# I2C_MUX.net
KiCad netlist of a schematic drawn in Altium Designer
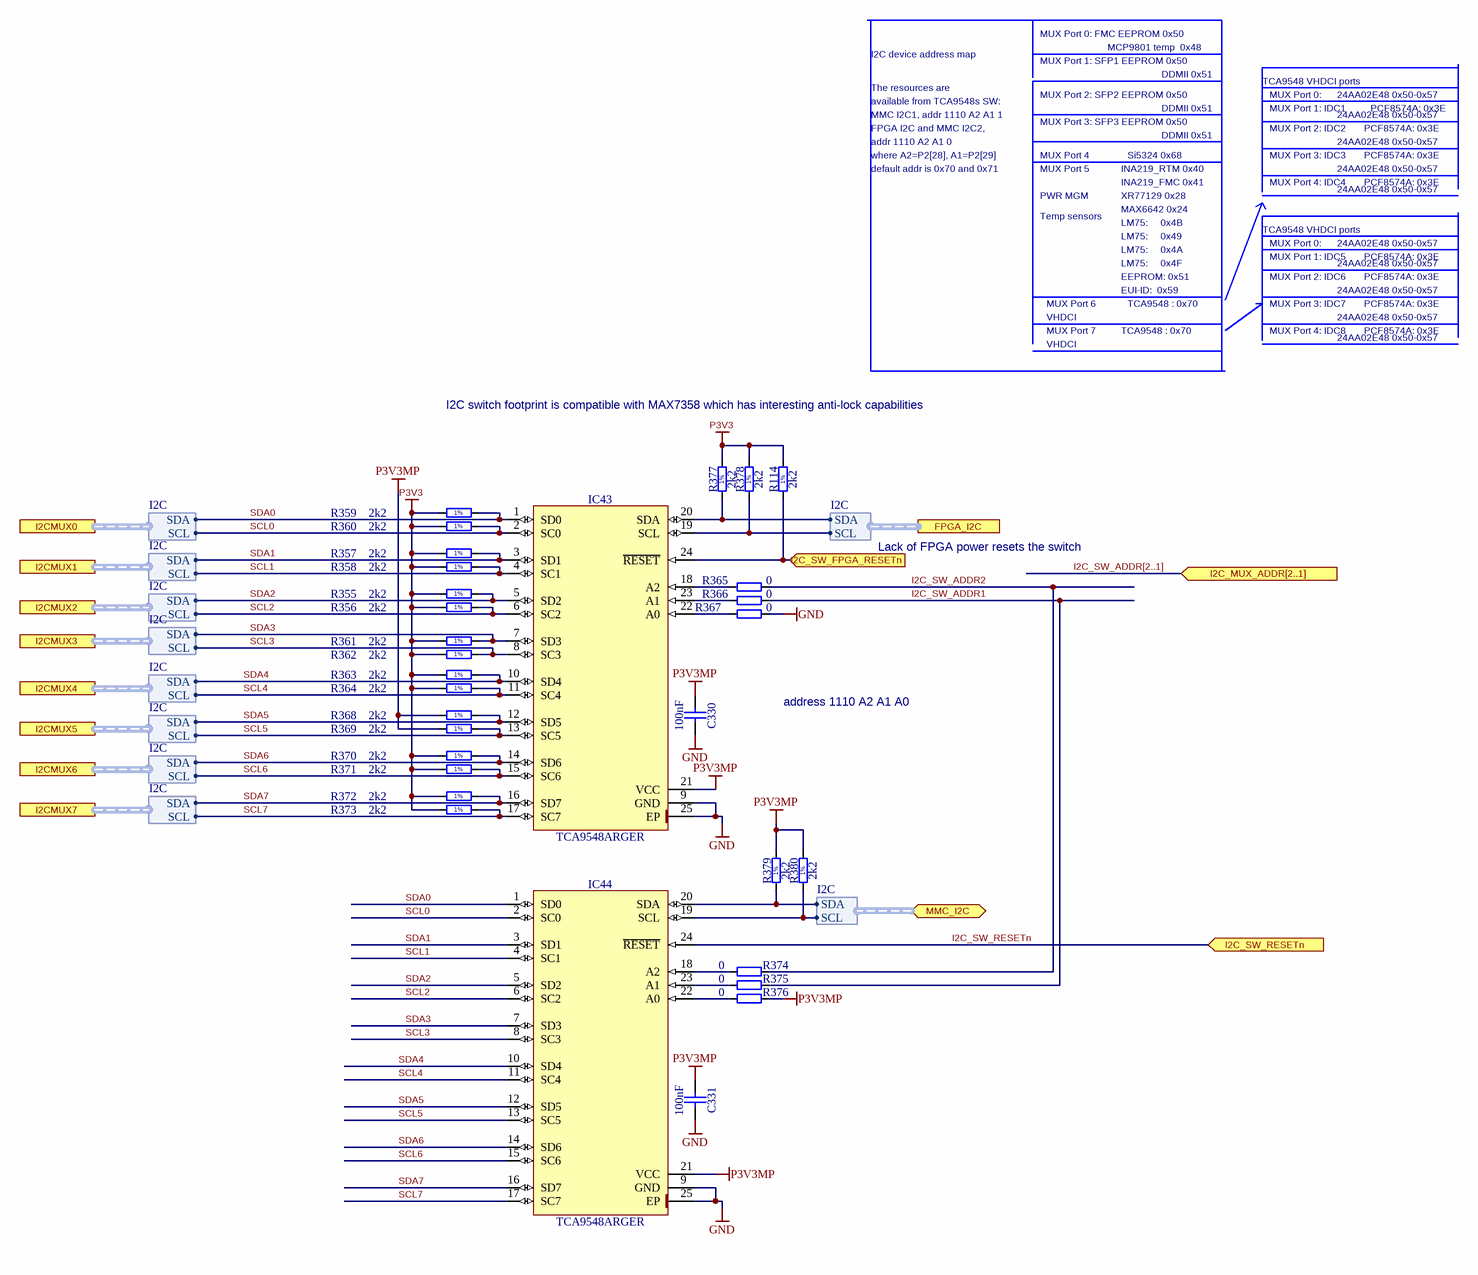
[diagram p0: I2C_MUX.SchDoc]

(export (version "E")
  (design (tool "Eeschema 10.0.6"))
  (components
    (comp (ref "C330")
      (value "100nF")
      (footprint "CAPC0603X33N")
      (description "Non-polarised capacitor")
      (fields
        (field (name "MANUFACTURER PART NUMBER") "CC0201_100NF_6.3V_10%_X5R")
        (field (name "MANUFACTURER") "GENERIC")
        (field (name "AUTHOR") "CERN DEM JLC")
      )
      (libsource (lib "Capacitors") (part "Capacitor - non polarized"))
    )
    (comp (ref "C331")
      (value "100nF")
      (footprint "CAPC0603X33N")
      (description "Non-polarised capacitor")
      (fields
        (field (name "MANUFACTURER PART NUMBER") "CC0201_100NF_6.3V_10%_X5R")
        (field (name "MANUFACTURER") "GENERIC")
        (field (name "AUTHOR") "CERN DEM JLC")
      )
      (libsource (lib "Capacitors") (part "Capacitor - non polarized"))
    )
    (comp (ref "IC43")
      (value "TCA9548ARGER")
      (footprint "QFN50P400X400X100-25N-S220")
      (description "Low Voltage 8-Channel I2C Switch With Reset")
      (fields (field (name "MANUFACTURER") "TEXAS INSTRUMENTS") (field (name "AUTHOR") "CERN DEM JLC"))
      (libsource (lib "ICs And Semiconductors") (part "TCA9548ARGER"))
    )
    (comp (ref "IC44")
      (value "TCA9548ARGER")
      (footprint "QFN50P400X400X100-25N-S220")
      (description "Low Voltage 8-Channel I2C Switch With Reset")
      (fields (field (name "MANUFACTURER") "TEXAS INSTRUMENTS") (field (name "AUTHOR") "CERN DEM JLC"))
      (libsource (lib "ICs And Semiconductors") (part "TCA9548ARGER"))
    )
    (comp (ref "R114")
      (value "2k2")
      (footprint "RESC1005X40N")
      (description "Resistor - 1%")
      (fields
        (field (name "MANUFACTURER PART NUMBER") "R0402_2K2_1%_0.0625W_100PPM")
        (field (name "MANUFACTURER") "GENERIC")
        (field (name "AUTHOR") "CERN DEM JLC")
      )
      (libsource (lib "Resistors") (part "Resistor - 1%"))
    )
    (comp (ref "R355")
      (value "2k2")
      (footprint "RESC1005X40N")
      (description "Resistor - 1%")
      (fields
        (field (name "MANUFACTURER PART NUMBER") "R0402_2K2_1%_0.0625W_100PPM")
        (field (name "MANUFACTURER") "GENERIC")
        (field (name "AUTHOR") "CERN DEM JLC")
      )
      (libsource (lib "Resistors") (part "Resistor - 1%"))
    )
    (comp (ref "R356")
      (value "2k2")
      (footprint "RESC1005X40N")
      (description "Resistor - 1%")
      (fields
        (field (name "MANUFACTURER PART NUMBER") "R0402_2K2_1%_0.0625W_100PPM")
        (field (name "MANUFACTURER") "GENERIC")
        (field (name "AUTHOR") "CERN DEM JLC")
      )
      (libsource (lib "Resistors") (part "Resistor - 1%"))
    )
    (comp (ref "R357")
      (value "2k2")
      (footprint "RESC1005X40N")
      (description "Resistor - 1%")
      (fields
        (field (name "MANUFACTURER PART NUMBER") "R0402_2K2_1%_0.0625W_100PPM")
        (field (name "MANUFACTURER") "GENERIC")
        (field (name "AUTHOR") "CERN DEM JLC")
      )
      (libsource (lib "Resistors") (part "Resistor - 1%"))
    )
    (comp (ref "R358")
      (value "2k2")
      (footprint "RESC1005X40N")
      (description "Resistor - 1%")
      (fields
        (field (name "MANUFACTURER PART NUMBER") "R0402_2K2_1%_0.0625W_100PPM")
        (field (name "MANUFACTURER") "GENERIC")
        (field (name "AUTHOR") "CERN DEM JLC")
      )
      (libsource (lib "Resistors") (part "Resistor - 1%"))
    )
    (comp (ref "R359")
      (value "2k2")
      (footprint "RESC1005X40N")
      (description "Resistor - 1%")
      (fields
        (field (name "MANUFACTURER PART NUMBER") "R0402_2K2_1%_0.0625W_100PPM")
        (field (name "MANUFACTURER") "GENERIC")
        (field (name "AUTHOR") "CERN DEM JLC")
      )
      (libsource (lib "Resistors") (part "Resistor - 1%"))
    )
    (comp (ref "R360")
      (value "2k2")
      (footprint "RESC1005X40N")
      (description "Resistor - 1%")
      (fields
        (field (name "MANUFACTURER PART NUMBER") "R0402_2K2_1%_0.0625W_100PPM")
        (field (name "MANUFACTURER") "GENERIC")
        (field (name "AUTHOR") "CERN DEM JLC")
      )
      (libsource (lib "Resistors") (part "Resistor - 1%"))
    )
    (comp (ref "R361")
      (value "2k2")
      (footprint "RESC1005X40N")
      (description "Resistor - 1%")
      (fields
        (field (name "MANUFACTURER PART NUMBER") "R0402_2K2_1%_0.0625W_100PPM")
        (field (name "MANUFACTURER") "GENERIC")
        (field (name "AUTHOR") "CERN DEM JLC")
      )
      (libsource (lib "Resistors") (part "Resistor - 1%"))
    )
    (comp (ref "R362")
      (value "2k2")
      (footprint "RESC1005X40N")
      (description "Resistor - 1%")
      (fields
        (field (name "MANUFACTURER PART NUMBER") "R0402_2K2_1%_0.0625W_100PPM")
        (field (name "MANUFACTURER") "GENERIC")
        (field (name "AUTHOR") "CERN DEM JLC")
      )
      (libsource (lib "Resistors") (part "Resistor - 1%"))
    )
    (comp (ref "R363")
      (value "2k2")
      (footprint "RESC1005X40N")
      (description "Resistor - 1%")
      (fields
        (field (name "MANUFACTURER PART NUMBER") "R0402_2K2_1%_0.0625W_100PPM")
        (field (name "MANUFACTURER") "GENERIC")
        (field (name "AUTHOR") "CERN DEM JLC")
      )
      (libsource (lib "Resistors") (part "Resistor - 1%"))
    )
    (comp (ref "R364")
      (value "2k2")
      (footprint "RESC1005X40N")
      (description "Resistor - 1%")
      (fields
        (field (name "MANUFACTURER PART NUMBER") "R0402_2K2_1%_0.0625W_100PPM")
        (field (name "MANUFACTURER") "GENERIC")
        (field (name "AUTHOR") "CERN DEM JLC")
      )
      (libsource (lib "Resistors") (part "Resistor - 1%"))
    )
    (comp (ref "R365")
      (value "0")
      (footprint "RESC1005X40N")
      (description "Resistor")
      (fields
        (field (name "MANUFACTURER PART NUMBER") "R0402_0R_JUMPER")
        (field (name "MANUFACTURER") "GENERIC")
        (field (name "AUTHOR") "CERN DEM JLC")
      )
      (libsource (lib "Resistors") (part "Resistor"))
    )
    (comp (ref "R366")
      (value "0")
      (footprint "RESC1005X40N")
      (description "Resistor")
      (fields
        (field (name "MANUFACTURER PART NUMBER") "R0402_0R_JUMPER")
        (field (name "MANUFACTURER") "GENERIC")
        (field (name "AUTHOR") "CERN DEM JLC")
      )
      (libsource (lib "Resistors") (part "Resistor"))
    )
    (comp (ref "R367")
      (value "0")
      (footprint "RESC1005X40N")
      (description "Resistor")
      (fields
        (field (name "MANUFACTURER PART NUMBER") "R0402_0R_JUMPER")
        (field (name "MANUFACTURER") "GENERIC")
        (field (name "AUTHOR") "CERN DEM JLC")
      )
      (libsource (lib "Resistors") (part "Resistor"))
    )
    (comp (ref "R368")
      (value "2k2")
      (footprint "RESC1005X40N")
      (description "Resistor - 1%")
      (fields
        (field (name "MANUFACTURER PART NUMBER") "R0402_2K2_1%_0.0625W_100PPM")
        (field (name "MANUFACTURER") "GENERIC")
        (field (name "AUTHOR") "CERN DEM JLC")
      )
      (libsource (lib "Resistors") (part "Resistor - 1%"))
    )
    (comp (ref "R369")
      (value "2k2")
      (footprint "RESC1005X40N")
      (description "Resistor - 1%")
      (fields
        (field (name "MANUFACTURER PART NUMBER") "R0402_2K2_1%_0.0625W_100PPM")
        (field (name "MANUFACTURER") "GENERIC")
        (field (name "AUTHOR") "CERN DEM JLC")
      )
      (libsource (lib "Resistors") (part "Resistor - 1%"))
    )
    (comp (ref "R370")
      (value "2k2")
      (footprint "RESC1005X40N")
      (description "Resistor - 1%")
      (fields
        (field (name "MANUFACTURER PART NUMBER") "R0402_2K2_1%_0.0625W_100PPM")
        (field (name "MANUFACTURER") "GENERIC")
        (field (name "AUTHOR") "CERN DEM JLC")
      )
      (libsource (lib "Resistors") (part "Resistor - 1%"))
    )
    (comp (ref "R371")
      (value "2k2")
      (footprint "RESC1005X40N")
      (description "Resistor - 1%")
      (fields
        (field (name "MANUFACTURER PART NUMBER") "R0402_2K2_1%_0.0625W_100PPM")
        (field (name "MANUFACTURER") "GENERIC")
        (field (name "AUTHOR") "CERN DEM JLC")
      )
      (libsource (lib "Resistors") (part "Resistor - 1%"))
    )
    (comp (ref "R372")
      (value "2k2")
      (footprint "RESC1005X40N")
      (description "Resistor - 1%")
      (fields
        (field (name "MANUFACTURER PART NUMBER") "R0402_2K2_1%_0.0625W_100PPM")
        (field (name "MANUFACTURER") "GENERIC")
        (field (name "AUTHOR") "CERN DEM JLC")
      )
      (libsource (lib "Resistors") (part "Resistor - 1%"))
    )
    (comp (ref "R373")
      (value "2k2")
      (footprint "RESC1005X40N")
      (description "Resistor - 1%")
      (fields
        (field (name "MANUFACTURER PART NUMBER") "R0402_2K2_1%_0.0625W_100PPM")
        (field (name "MANUFACTURER") "GENERIC")
        (field (name "AUTHOR") "CERN DEM JLC")
      )
      (libsource (lib "Resistors") (part "Resistor - 1%"))
    )
    (comp (ref "R374")
      (value "0")
      (footprint "RESC1005X40N")
      (description "Resistor")
      (fields
        (field (name "MANUFACTURER PART NUMBER") "R0402_0R_JUMPER")
        (field (name "MANUFACTURER") "GENERIC")
        (field (name "AUTHOR") "CERN DEM JLC")
      )
      (libsource (lib "Resistors") (part "Resistor"))
    )
    (comp (ref "R375")
      (value "0")
      (footprint "RESC1005X40N")
      (description "Resistor")
      (fields
        (field (name "MANUFACTURER PART NUMBER") "R0402_0R_JUMPER")
        (field (name "MANUFACTURER") "GENERIC")
        (field (name "AUTHOR") "CERN DEM JLC")
      )
      (libsource (lib "Resistors") (part "Resistor"))
    )
    (comp (ref "R376")
      (value "0")
      (footprint "RESC1005X40N")
      (description "Resistor")
      (fields
        (field (name "MANUFACTURER PART NUMBER") "R0402_0R_JUMPER")
        (field (name "MANUFACTURER") "GENERIC")
        (field (name "AUTHOR") "CERN DEM JLC")
      )
      (libsource (lib "Resistors") (part "Resistor"))
    )
    (comp (ref "R377")
      (value "2k2")
      (footprint "RESC1005X40N")
      (description "Resistor - 1%")
      (fields
        (field (name "MANUFACTURER PART NUMBER") "R0402_2K2_1%_0.0625W_100PPM")
        (field (name "MANUFACTURER") "GENERIC")
        (field (name "AUTHOR") "CERN DEM JLC")
      )
      (libsource (lib "Resistors") (part "Resistor - 1%"))
    )
    (comp (ref "R378")
      (value "2k2")
      (footprint "RESC1005X40N")
      (description "Resistor - 1%")
      (fields
        (field (name "MANUFACTURER PART NUMBER") "R0402_2K2_1%_0.0625W_100PPM")
        (field (name "MANUFACTURER") "GENERIC")
        (field (name "AUTHOR") "CERN DEM JLC")
      )
      (libsource (lib "Resistors") (part "Resistor - 1%"))
    )
    (comp (ref "R379")
      (value "2k2")
      (footprint "RESC1005X40N")
      (description "Resistor - 1%")
      (fields
        (field (name "MANUFACTURER PART NUMBER") "R0402_2K2_1%_0.0625W_100PPM")
        (field (name "MANUFACTURER") "GENERIC")
        (field (name "AUTHOR") "CERN DEM JLC")
      )
      (libsource (lib "Resistors") (part "Resistor - 1%"))
    )
    (comp (ref "R380")
      (value "2k2")
      (footprint "RESC1005X40N")
      (description "Resistor - 1%")
      (fields
        (field (name "MANUFACTURER PART NUMBER") "R0402_2K2_1%_0.0625W_100PPM")
        (field (name "MANUFACTURER") "GENERIC")
        (field (name "AUTHOR") "CERN DEM JLC")
      )
      (libsource (lib "Resistors") (part "Resistor - 1%"))
    )
  )
  (nets
    (net (code "2") (name "/I2C_SW_ADDR1") (class "Default")
      (node (ref "R366") (pin "1") (pinfunction "1_1") (pintype "passive"))
      (node (ref "R375") (pin "1") (pinfunction "1_1") (pintype "passive"))
    )
    (net (code "3") (name "/I2C_SW_ADDR2") (class "Default")
      (node (ref "R365") (pin "1") (pinfunction "1_1") (pintype "passive"))
      (node (ref "R374") (pin "1") (pinfunction "1_1") (pintype "passive"))
    )
    (net (code "5") (name "/I2C_SW_FPGA_RESETn") (class "Default")
      (node (ref "IC43") (pin "24") (pinfunction "~{RESET}_24") (pintype "input"))
      (node (ref "R114") (pin "1") (pinfunction "1_1") (pintype "passive"))
    )
    (net (code "6") (name "/I2C_SW_RESETn") (class "Default")
      (node (ref "IC44") (pin "24") (pinfunction "~{RESET}_24") (pintype "input"))
    )
    (net (code "7") (name "/SCL0") (class "Default")
      (node (ref "IC43") (pin "2") (pinfunction "SC0_2") (pintype "bidirectional"))
      (node (ref "IC44") (pin "2") (pinfunction "SC0_2") (pintype "bidirectional"))
      (node (ref "R360") (pin "2") (pinfunction "2_2") (pintype "passive"))
    )
    (net (code "8") (name "/SCL1") (class "Default")
      (node (ref "IC43") (pin "4") (pinfunction "SC1_4") (pintype "bidirectional"))
      (node (ref "IC44") (pin "4") (pinfunction "SC1_4") (pintype "bidirectional"))
      (node (ref "R358") (pin "2") (pinfunction "2_2") (pintype "passive"))
    )
    (net (code "9") (name "/SCL2") (class "Default")
      (node (ref "IC43") (pin "6") (pinfunction "SC2_6") (pintype "bidirectional"))
      (node (ref "IC44") (pin "6") (pinfunction "SC2_6") (pintype "bidirectional"))
      (node (ref "R356") (pin "2") (pinfunction "2_2") (pintype "passive"))
    )
    (net (code "10") (name "/SCL3") (class "Default")
      (node (ref "IC43") (pin "8") (pinfunction "SC3_8") (pintype "bidirectional"))
      (node (ref "IC44") (pin "8") (pinfunction "SC3_8") (pintype "bidirectional"))
      (node (ref "R362") (pin "2") (pinfunction "2_2") (pintype "passive"))
    )
    (net (code "11") (name "/SCL4") (class "Default")
      (node (ref "IC43") (pin "11") (pinfunction "SC4_11") (pintype "bidirectional"))
      (node (ref "IC44") (pin "11") (pinfunction "SC4_11") (pintype "bidirectional"))
      (node (ref "R364") (pin "2") (pinfunction "2_2") (pintype "passive"))
    )
    (net (code "12") (name "/SCL5") (class "Default")
      (node (ref "IC43") (pin "13") (pinfunction "SC5_13") (pintype "bidirectional"))
      (node (ref "IC44") (pin "13") (pinfunction "SC5_13") (pintype "bidirectional"))
      (node (ref "R369") (pin "2") (pinfunction "2_2") (pintype "passive"))
    )
    (net (code "13") (name "/SCL6") (class "Default")
      (node (ref "IC43") (pin "15") (pinfunction "SC6_15") (pintype "bidirectional"))
      (node (ref "IC44") (pin "15") (pinfunction "SC6_15") (pintype "bidirectional"))
      (node (ref "R371") (pin "2") (pinfunction "2_2") (pintype "passive"))
    )
    (net (code "14") (name "/SCL7") (class "Default")
      (node (ref "IC43") (pin "17") (pinfunction "SC7_17") (pintype "bidirectional"))
      (node (ref "IC44") (pin "17") (pinfunction "SC7_17") (pintype "bidirectional"))
      (node (ref "R373") (pin "2") (pinfunction "2_2") (pintype "passive"))
    )
    (net (code "15") (name "/SDA0") (class "Default")
      (node (ref "IC43") (pin "1") (pinfunction "SD0_1") (pintype "bidirectional"))
      (node (ref "IC44") (pin "1") (pinfunction "SD0_1") (pintype "bidirectional"))
      (node (ref "R359") (pin "2") (pinfunction "2_2") (pintype "passive"))
    )
    (net (code "16") (name "/SDA1") (class "Default")
      (node (ref "IC43") (pin "3") (pinfunction "SD1_3") (pintype "bidirectional"))
      (node (ref "IC44") (pin "3") (pinfunction "SD1_3") (pintype "bidirectional"))
      (node (ref "R357") (pin "2") (pinfunction "2_2") (pintype "passive"))
    )
    (net (code "17") (name "/SDA2") (class "Default")
      (node (ref "IC43") (pin "5") (pinfunction "SD2_5") (pintype "bidirectional"))
      (node (ref "IC44") (pin "5") (pinfunction "SD2_5") (pintype "bidirectional"))
      (node (ref "R355") (pin "2") (pinfunction "2_2") (pintype "passive"))
    )
    (net (code "18") (name "/SDA3") (class "Default")
      (node (ref "IC43") (pin "7") (pinfunction "SD3_7") (pintype "bidirectional"))
      (node (ref "IC44") (pin "7") (pinfunction "SD3_7") (pintype "bidirectional"))
      (node (ref "R361") (pin "2") (pinfunction "2_2") (pintype "passive"))
    )
    (net (code "19") (name "/SDA4") (class "Default")
      (node (ref "IC43") (pin "10") (pinfunction "SD4_10") (pintype "bidirectional"))
      (node (ref "IC44") (pin "10") (pinfunction "SD4_10") (pintype "bidirectional"))
      (node (ref "R363") (pin "2") (pinfunction "2_2") (pintype "passive"))
    )
    (net (code "20") (name "/SDA5") (class "Default")
      (node (ref "IC43") (pin "12") (pinfunction "SD5_12") (pintype "bidirectional"))
      (node (ref "IC44") (pin "12") (pinfunction "SD5_12") (pintype "bidirectional"))
      (node (ref "R368") (pin "2") (pinfunction "2_2") (pintype "passive"))
    )
    (net (code "21") (name "/SDA6") (class "Default")
      (node (ref "IC43") (pin "14") (pinfunction "SD6_14") (pintype "bidirectional"))
      (node (ref "IC44") (pin "14") (pinfunction "SD6_14") (pintype "bidirectional"))
      (node (ref "R370") (pin "2") (pinfunction "2_2") (pintype "passive"))
    )
    (net (code "22") (name "/SDA7") (class "Default")
      (node (ref "IC43") (pin "16") (pinfunction "SD7_16") (pintype "bidirectional"))
      (node (ref "IC44") (pin "16") (pinfunction "SD7_16") (pintype "bidirectional"))
      (node (ref "R372") (pin "2") (pinfunction "2_2") (pintype "passive"))
    )
    (net (code "24") (name "GND") (class "Default")
      (node (ref "C330") (pin "2") (pinfunction "2_2") (pintype "passive"))
      (node (ref "C331") (pin "2") (pinfunction "2_2") (pintype "passive"))
      (node (ref "IC43") (pin "25") (pinfunction "EP_25") (pintype "power_in"))
      (node (ref "IC43") (pin "9") (pinfunction "GND_9") (pintype "power_in"))
      (node (ref "IC44") (pin "25") (pinfunction "EP_25") (pintype "power_in"))
      (node (ref "IC44") (pin "9") (pinfunction "GND_9") (pintype "power_in"))
      (node (ref "R367") (pin "1") (pinfunction "1_1") (pintype "passive"))
    )
    (net (code "25") (name "Net-(IC43-A0)") (class "Default")
      (node (ref "IC43") (pin "22") (pinfunction "A0_22") (pintype "input"))
      (node (ref "R367") (pin "2") (pinfunction "2_2") (pintype "passive"))
    )
    (net (code "26") (name "Net-(IC43-A1)") (class "Default")
      (node (ref "IC43") (pin "23") (pinfunction "A1_23") (pintype "input"))
      (node (ref "R366") (pin "2") (pinfunction "2_2") (pintype "passive"))
    )
    (net (code "27") (name "Net-(IC43-A2)") (class "Default")
      (node (ref "IC43") (pin "18") (pinfunction "A2_18") (pintype "input"))
      (node (ref "R365") (pin "2") (pinfunction "2_2") (pintype "passive"))
    )
    (net (code "28") (name "Net-(IC43-SCL)") (class "Default")
      (node (ref "IC43") (pin "19") (pinfunction "SCL_19") (pintype "bidirectional"))
      (node (ref "R378") (pin "1") (pinfunction "1_1") (pintype "passive"))
    )
    (net (code "29") (name "Net-(IC43-SDA)") (class "Default")
      (node (ref "IC43") (pin "20") (pinfunction "SDA_20") (pintype "bidirectional"))
      (node (ref "R377") (pin "1") (pinfunction "1_1") (pintype "passive"))
    )
    (net (code "30") (name "Net-(IC44-A0)") (class "Default")
      (node (ref "IC44") (pin "22") (pinfunction "A0_22") (pintype "input"))
      (node (ref "R376") (pin "2") (pinfunction "2_2") (pintype "passive"))
    )
    (net (code "31") (name "Net-(IC44-A1)") (class "Default")
      (node (ref "IC44") (pin "23") (pinfunction "A1_23") (pintype "input"))
      (node (ref "R375") (pin "2") (pinfunction "2_2") (pintype "passive"))
    )
    (net (code "32") (name "Net-(IC44-A2)") (class "Default")
      (node (ref "IC44") (pin "18") (pinfunction "A2_18") (pintype "input"))
      (node (ref "R374") (pin "2") (pinfunction "2_2") (pintype "passive"))
    )
    (net (code "33") (name "Net-(IC44-SCL)") (class "Default")
      (node (ref "IC44") (pin "19") (pinfunction "SCL_19") (pintype "bidirectional"))
      (node (ref "R380") (pin "1") (pinfunction "1_1") (pintype "passive"))
    )
    (net (code "34") (name "Net-(IC44-SDA)") (class "Default")
      (node (ref "IC44") (pin "20") (pinfunction "SDA_20") (pintype "bidirectional"))
      (node (ref "R379") (pin "1") (pinfunction "1_1") (pintype "passive"))
    )
    (net (code "35") (name "P3V3") (class "Default")
      (node (ref "R114") (pin "2") (pinfunction "2_2") (pintype "passive"))
      (node (ref "R355") (pin "1") (pinfunction "1_1") (pintype "passive"))
      (node (ref "R356") (pin "1") (pinfunction "1_1") (pintype "passive"))
      (node (ref "R357") (pin "1") (pinfunction "1_1") (pintype "passive"))
      (node (ref "R358") (pin "1") (pinfunction "1_1") (pintype "passive"))
      (node (ref "R359") (pin "1") (pinfunction "1_1") (pintype "passive"))
      (node (ref "R360") (pin "1") (pinfunction "1_1") (pintype "passive"))
      (node (ref "R361") (pin "1") (pinfunction "1_1") (pintype "passive"))
      (node (ref "R362") (pin "1") (pinfunction "1_1") (pintype "passive"))
      (node (ref "R363") (pin "1") (pinfunction "1_1") (pintype "passive"))
      (node (ref "R364") (pin "1") (pinfunction "1_1") (pintype "passive"))
      (node (ref "R370") (pin "1") (pinfunction "1_1") (pintype "passive"))
      (node (ref "R371") (pin "1") (pinfunction "1_1") (pintype "passive"))
      (node (ref "R372") (pin "1") (pinfunction "1_1") (pintype "passive"))
      (node (ref "R373") (pin "1") (pinfunction "1_1") (pintype "passive"))
      (node (ref "R377") (pin "2") (pinfunction "2_2") (pintype "passive"))
      (node (ref "R378") (pin "2") (pinfunction "2_2") (pintype "passive"))
    )
    (net (code "36") (name "P3V3MP") (class "Default")
      (node (ref "C330") (pin "1") (pinfunction "1_1") (pintype "passive"))
      (node (ref "C331") (pin "1") (pinfunction "1_1") (pintype "passive"))
      (node (ref "IC43") (pin "21") (pinfunction "VCC_21") (pintype "power_in"))
      (node (ref "IC44") (pin "21") (pinfunction "VCC_21") (pintype "power_in"))
      (node (ref "R368") (pin "1") (pinfunction "1_1") (pintype "passive"))
      (node (ref "R369") (pin "1") (pinfunction "1_1") (pintype "passive"))
      (node (ref "R376") (pin "1") (pinfunction "1_1") (pintype "passive"))
      (node (ref "R379") (pin "2") (pinfunction "2_2") (pintype "passive"))
      (node (ref "R380") (pin "2") (pinfunction "2_2") (pintype "passive"))
    )
  )
)
